# schematic.net
KiCad netlist of a schematic drawn in EAGLE
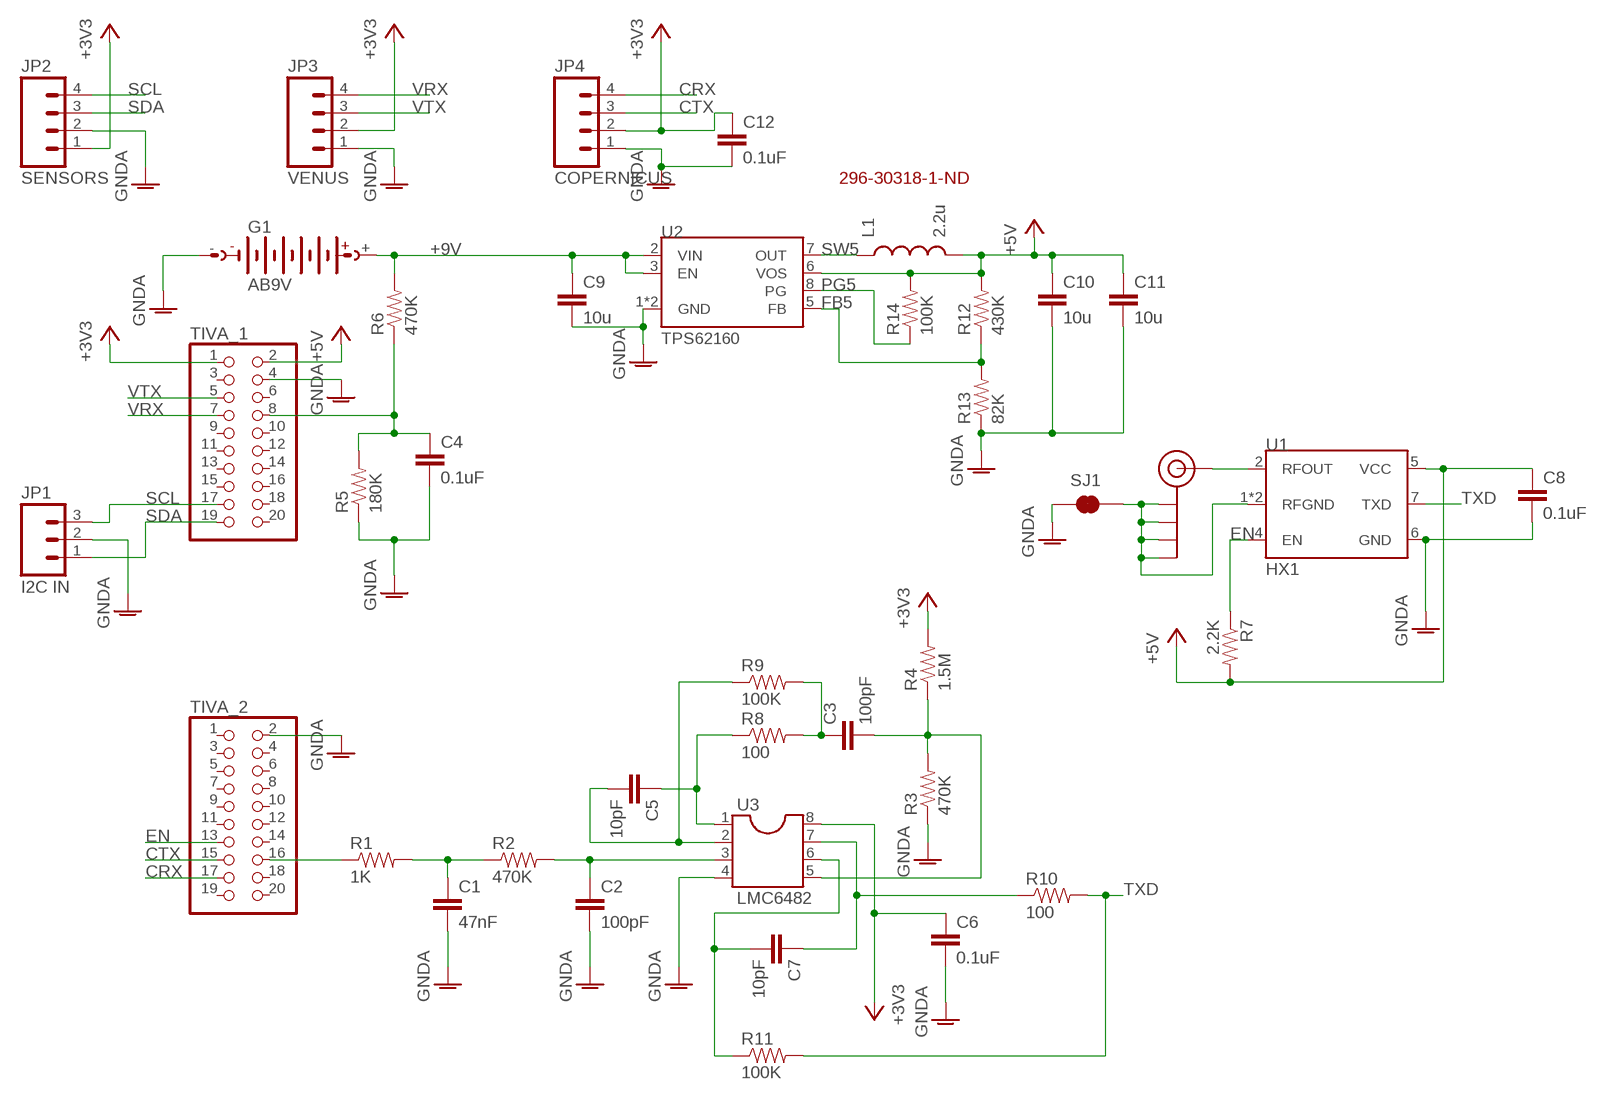
[diagram p0: schematic, sheet 1]

(export (version "E")
  (design (tool "Eeschema 10.0.6"))
  (components
    (comp (ref "C1")
      (value "47nF")
      (footprint "eagle-import:0805")
      (libsource (lib "eagle-import") (part "CAP0805"))
    )
    (comp (ref "C2")
      (value "100pF")
      (footprint "eagle-import:0805")
      (libsource (lib "eagle-import") (part "CAP0805"))
    )
    (comp (ref "C3")
      (value "100pF")
      (footprint "eagle-import:0805")
      (libsource (lib "eagle-import") (part "CAP0805"))
    )
    (comp (ref "C4")
      (value "0.1uF")
      (footprint "eagle-import:0805")
      (libsource (lib "eagle-import") (part "CAP0805"))
    )
    (comp (ref "C5")
      (value "10pF")
      (footprint "eagle-import:0805")
      (libsource (lib "eagle-import") (part "CAP0805"))
    )
    (comp (ref "C6")
      (value "0.1uF")
      (footprint "eagle-import:0805")
      (libsource (lib "eagle-import") (part "CAP0805"))
    )
    (comp (ref "C7")
      (value "10pF")
      (footprint "eagle-import:0805")
      (libsource (lib "eagle-import") (part "CAP0805"))
    )
    (comp (ref "C8")
      (value "0.1uF")
      (footprint "eagle-import:0805")
      (libsource (lib "eagle-import") (part "CAP0805"))
    )
    (comp (ref "C9")
      (value "10u")
      (footprint "eagle-import:0805")
      (libsource (lib "eagle-import") (part "CAP0805"))
    )
    (comp (ref "C10")
      (value "10u")
      (footprint "eagle-import:0805")
      (libsource (lib "eagle-import") (part "CAP0805"))
    )
    (comp (ref "C11")
      (value "10u")
      (footprint "eagle-import:0805")
      (libsource (lib "eagle-import") (part "CAP0805"))
    )
    (comp (ref "C12")
      (value "0.1uF")
      (footprint "eagle-import:0805")
      (libsource (lib "eagle-import") (part "CAP0805"))
    )
    (comp (ref "G1")
      (value "AB9V")
      (footprint "eagle-import:AB9V")
      (libsource (lib "eagle-import") (part "AB9V"))
    )
    (comp (ref "J1")
      (value "SMA_EDGE")
      (footprint "eagle-import:SMA-EDGE")
      (libsource (lib "eagle-import") (part "SMA_EDGE"))
    )
    (comp (ref "JP1")
      (value "I2C IN")
      (footprint "eagle-import:1X03")
      (libsource (lib "eagle-import") (part "M03PTH"))
    )
    (comp (ref "JP2")
      (value "SENSORS")
      (footprint "eagle-import:1X04")
      (libsource (lib "eagle-import") (part "M04PTH"))
    )
    (comp (ref "JP3")
      (value "VENUS")
      (footprint "eagle-import:1X04")
      (libsource (lib "eagle-import") (part "M04PTH"))
    )
    (comp (ref "JP4")
      (value "COPERNICUS")
      (footprint "eagle-import:1X04")
      (libsource (lib "eagle-import") (part "M04PTH"))
    )
    (comp (ref "L1")
      (value "2.2u")
      (footprint "eagle-import:1008")
      (libsource (lib "eagle-import") (part "INDUCTOR"))
    )
    (comp (ref "R1")
      (value "1K")
      (footprint "eagle-import:0805")
      (libsource (lib "eagle-import") (part "RESISTOR0805-RES"))
    )
    (comp (ref "R2")
      (value "470K")
      (footprint "eagle-import:0805")
      (libsource (lib "eagle-import") (part "RESISTOR0805-RES"))
    )
    (comp (ref "R3")
      (value "470K")
      (footprint "eagle-import:0805")
      (libsource (lib "eagle-import") (part "RESISTOR0805-RES"))
    )
    (comp (ref "R4")
      (value "1.5M")
      (footprint "eagle-import:0805")
      (libsource (lib "eagle-import") (part "RESISTOR0805-RES"))
    )
    (comp (ref "R5")
      (value "180K")
      (footprint "eagle-import:0805")
      (libsource (lib "eagle-import") (part "RESISTOR0805-RES"))
    )
    (comp (ref "R6")
      (value "470K")
      (footprint "eagle-import:0805")
      (libsource (lib "eagle-import") (part "RESISTOR0805-RES"))
    )
    (comp (ref "R7")
      (value "2.2K")
      (footprint "eagle-import:0805")
      (libsource (lib "eagle-import") (part "RESISTOR0805-RES"))
    )
    (comp (ref "R8")
      (value "100")
      (footprint "eagle-import:0805")
      (libsource (lib "eagle-import") (part "RESISTOR0805-RES"))
    )
    (comp (ref "R9")
      (value "100K")
      (footprint "eagle-import:0805")
      (libsource (lib "eagle-import") (part "RESISTOR0805-RES"))
    )
    (comp (ref "R10")
      (value "100")
      (footprint "eagle-import:0805")
      (libsource (lib "eagle-import") (part "RESISTOR0805-RES"))
    )
    (comp (ref "R11")
      (value "100K")
      (footprint "eagle-import:0805")
      (libsource (lib "eagle-import") (part "RESISTOR0805-RES"))
    )
    (comp (ref "R12")
      (value "430K")
      (footprint "eagle-import:0805")
      (libsource (lib "eagle-import") (part "RESISTOR0805-RES"))
    )
    (comp (ref "R13")
      (value "82K")
      (footprint "eagle-import:0805")
      (libsource (lib "eagle-import") (part "RESISTOR0805-RES"))
    )
    (comp (ref "R14")
      (value "100K")
      (footprint "eagle-import:0805")
      (libsource (lib "eagle-import") (part "RESISTOR0805-RES"))
    )
    (comp (ref "SJ1")
      (value "JUMPER-PAD-2-NC_BY_TRACE")
      (footprint "eagle-import:PAD-JUMPER-2-NC_BY_TRACE_YES_SILK")
      (libsource (lib "eagle-import") (part "JUMPER-PAD-2-NC_BY_TRACE"))
    )
    (comp (ref "TIVA_1")
      (value "PINHD-2X10")
      (footprint "eagle-import:2X10")
      (libsource (lib "eagle-import") (part "PINHD-2X10"))
    )
    (comp (ref "TIVA_2")
      (value "PINHD-2X10")
      (footprint "eagle-import:2X10")
      (libsource (lib "eagle-import") (part "PINHD-2X10"))
    )
    (comp (ref "U1")
      (value "HX1")
      (footprint "eagle-import:1X12")
      (libsource (lib "eagle-import") (part "HX1"))
    )
    (comp (ref "U2")
      (value "TPS62160")
      (footprint "eagle-import:MSOP8")
      (libsource (lib "eagle-import") (part "TPS62160"))
    )
    (comp (ref "U3")
      (value "LMC6482")
      (footprint "eagle-import:DIL08")
      (libsource (lib "eagle-import") (part "DIL8"))
    )
  )
  (nets
    (net (code "1") (name "+3V3") (class "Default")
      (node (ref "C12") (pin "1") (pinfunction "1_1") (pintype "passive"))
      (node (ref "C6") (pin "1") (pinfunction "1_1") (pintype "passive"))
      (node (ref "JP2") (pin "1") (pinfunction "1_1") (pintype "passive"))
      (node (ref "JP3") (pin "2") (pinfunction "2_2") (pintype "passive"))
      (node (ref "JP4") (pin "2") (pinfunction "2_2") (pintype "passive"))
      (node (ref "R4") (pin "2") (pinfunction "2_2") (pintype "passive"))
      (node (ref "TIVA_1") (pin "1") (pinfunction "1_1") (pintype "passive"))
      (node (ref "U3") (pin "8") (pinfunction "8_8") (pintype "passive"))
    )
    (net (code "2") (name "+5V") (class "Default")
      (node (ref "C10") (pin "1") (pinfunction "1_1") (pintype "passive"))
      (node (ref "C11") (pin "1") (pinfunction "1_1") (pintype "passive"))
      (node (ref "C8") (pin "1") (pinfunction "1_1") (pintype "passive"))
      (node (ref "L1") (pin "2") (pinfunction "2_2") (pintype "passive"))
      (node (ref "R12") (pin "2") (pinfunction "2_2") (pintype "passive"))
      (node (ref "R14") (pin "2") (pinfunction "2_2") (pintype "passive"))
      (node (ref "R7") (pin "2") (pinfunction "2_2") (pintype "passive"))
      (node (ref "TIVA_1") (pin "2") (pinfunction "2_2") (pintype "passive"))
      (node (ref "U1") (pin "5") (pinfunction "VCC_5") (pintype "power_in"))
      (node (ref "U2") (pin "6") (pinfunction "VOS_6") (pintype "input"))
    )
    (net (code "3") (name "/+9V") (class "Default")
      (node (ref "C9") (pin "1") (pinfunction "1_1") (pintype "passive"))
      (node (ref "G1") (pin "+") (pinfunction "+_+") (pintype "passive"))
      (node (ref "R6") (pin "2") (pinfunction "2_2") (pintype "passive"))
      (node (ref "U2") (pin "2") (pinfunction "VIN_2") (pintype "power_in"))
      (node (ref "U2") (pin "3") (pinfunction "EN_3") (pintype "input"))
    )
    (net (code "4") (name "/CRX") (class "Default")
      (node (ref "JP4") (pin "4") (pinfunction "4_4") (pintype "passive"))
      (node (ref "TIVA_2") (pin "17") (pinfunction "17_17") (pintype "passive"))
    )
    (net (code "5") (name "/CTX") (class "Default")
      (node (ref "JP4") (pin "3") (pinfunction "3_3") (pintype "passive"))
      (node (ref "TIVA_2") (pin "15") (pinfunction "15_15") (pintype "passive"))
    )
    (net (code "6") (name "/EN") (class "Default")
      (node (ref "R7") (pin "1") (pinfunction "1_1") (pintype "passive"))
      (node (ref "TIVA_2") (pin "13") (pinfunction "13_13") (pintype "passive"))
      (node (ref "U1") (pin "4") (pinfunction "EN_4") (pintype "input"))
    )
    (net (code "7") (name "/FB5") (class "Default")
      (node (ref "R12") (pin "1") (pinfunction "1_1") (pintype "passive"))
      (node (ref "R13") (pin "2") (pinfunction "2_2") (pintype "passive"))
      (node (ref "U2") (pin "5") (pinfunction "FB_5") (pintype "input"))
    )
    (net (code "8") (name "/PG5") (class "Default")
      (node (ref "R14") (pin "1") (pinfunction "1_1") (pintype "passive"))
      (node (ref "U2") (pin "8") (pinfunction "PG_8") (pintype "open_collector"))
    )
    (net (code "9") (name "/SCL") (class "Default")
      (node (ref "JP1") (pin "3") (pinfunction "3_3") (pintype "passive"))
      (node (ref "JP2") (pin "4") (pinfunction "4_4") (pintype "passive"))
      (node (ref "TIVA_1") (pin "17") (pinfunction "17_17") (pintype "passive"))
    )
    (net (code "10") (name "/SDA") (class "Default")
      (node (ref "JP1") (pin "1") (pinfunction "1_1") (pintype "passive"))
      (node (ref "JP2") (pin "3") (pinfunction "3_3") (pintype "passive"))
      (node (ref "TIVA_1") (pin "19") (pinfunction "19_19") (pintype "passive"))
    )
    (net (code "11") (name "/SW5") (class "Default")
      (node (ref "L1") (pin "1") (pinfunction "1_1") (pintype "passive"))
      (node (ref "U2") (pin "7") (pinfunction "OUT_7") (pintype "output"))
    )
    (net (code "12") (name "/TXD") (class "Default")
      (node (ref "R10") (pin "2") (pinfunction "2_2") (pintype "passive"))
      (node (ref "R11") (pin "2") (pinfunction "2_2") (pintype "passive"))
      (node (ref "U1") (pin "7") (pinfunction "TXD_7") (pintype "input"))
    )
    (net (code "13") (name "/VRX") (class "Default")
      (node (ref "JP3") (pin "4") (pinfunction "4_4") (pintype "passive"))
      (node (ref "TIVA_1") (pin "7") (pinfunction "7_7") (pintype "passive"))
    )
    (net (code "14") (name "/VTX") (class "Default")
      (node (ref "JP3") (pin "3") (pinfunction "3_3") (pintype "passive"))
      (node (ref "TIVA_1") (pin "5") (pinfunction "5_5") (pintype "passive"))
    )
    (net (code "15") (name "GNDA") (class "Default")
      (node (ref "C1") (pin "2") (pinfunction "2_2") (pintype "passive"))
      (node (ref "C10") (pin "2") (pinfunction "2_2") (pintype "passive"))
      (node (ref "C11") (pin "2") (pinfunction "2_2") (pintype "passive"))
      (node (ref "C12") (pin "2") (pinfunction "2_2") (pintype "passive"))
      (node (ref "C2") (pin "2") (pinfunction "2_2") (pintype "passive"))
      (node (ref "C4") (pin "2") (pinfunction "2_2") (pintype "passive"))
      (node (ref "C6") (pin "2") (pinfunction "2_2") (pintype "passive"))
      (node (ref "C8") (pin "2") (pinfunction "2_2") (pintype "passive"))
      (node (ref "C9") (pin "2") (pinfunction "2_2") (pintype "passive"))
      (node (ref "G1") (pin "-") (pinfunction "-_-") (pintype "passive"))
      (node (ref "JP1") (pin "2") (pinfunction "2_2") (pintype "passive"))
      (node (ref "JP2") (pin "2") (pinfunction "2_2") (pintype "passive"))
      (node (ref "JP3") (pin "1") (pinfunction "1_1") (pintype "passive"))
      (node (ref "JP4") (pin "1") (pinfunction "1_1") (pintype "passive"))
      (node (ref "R13") (pin "1") (pinfunction "1_1") (pintype "passive"))
      (node (ref "R3") (pin "1") (pinfunction "1_1") (pintype "passive"))
      (node (ref "R5") (pin "1") (pinfunction "1_1") (pintype "passive"))
      (node (ref "SJ1") (pin "1") (pinfunction "1_1") (pintype "passive"))
      (node (ref "TIVA_1") (pin "4") (pinfunction "4_4") (pintype "passive"))
      (node (ref "TIVA_2") (pin "2") (pinfunction "2_2") (pintype "passive"))
      (node (ref "U1") (pin "6") (pinfunction "GND_6") (pintype "power_in"))
      (node (ref "U2") (pin "1") (pinfunction "GND_1") (pintype "power_in"))
      (node (ref "U2") (pin "4") (pinfunction "GND_4") (pintype "power_in"))
      (node (ref "U3") (pin "4") (pinfunction "4_4") (pintype "passive"))
    )
    (net (code "16") (name "Net-(C1-Pad1)") (class "Default")
      (node (ref "C1") (pin "1") (pinfunction "1_1") (pintype "passive"))
      (node (ref "R1") (pin "2") (pinfunction "2_2") (pintype "passive"))
      (node (ref "R2") (pin "1") (pinfunction "1_1") (pintype "passive"))
    )
    (net (code "17") (name "Net-(C2-Pad1)") (class "Default")
      (node (ref "C2") (pin "1") (pinfunction "1_1") (pintype "passive"))
      (node (ref "R2") (pin "2") (pinfunction "2_2") (pintype "passive"))
      (node (ref "U3") (pin "3") (pinfunction "3_3") (pintype "passive"))
    )
    (net (code "18") (name "Net-(C3-Pad1)") (class "Default")
      (node (ref "C3") (pin "1") (pinfunction "1_1") (pintype "passive"))
      (node (ref "R8") (pin "2") (pinfunction "2_2") (pintype "passive"))
      (node (ref "R9") (pin "2") (pinfunction "2_2") (pintype "passive"))
    )
    (net (code "19") (name "Net-(C3-Pad2)") (class "Default")
      (node (ref "C3") (pin "2") (pinfunction "2_2") (pintype "passive"))
      (node (ref "R3") (pin "2") (pinfunction "2_2") (pintype "passive"))
      (node (ref "R4") (pin "1") (pinfunction "1_1") (pintype "passive"))
      (node (ref "U3") (pin "5") (pinfunction "5_5") (pintype "passive"))
    )
    (net (code "20") (name "Net-(C4-Pad1)") (class "Default")
      (node (ref "C4") (pin "1") (pinfunction "1_1") (pintype "passive"))
      (node (ref "R5") (pin "2") (pinfunction "2_2") (pintype "passive"))
      (node (ref "R6") (pin "1") (pinfunction "1_1") (pintype "passive"))
      (node (ref "TIVA_1") (pin "8") (pinfunction "8_8") (pintype "passive"))
    )
    (net (code "21") (name "Net-(C5-Pad1)") (class "Default")
      (node (ref "C5") (pin "1") (pinfunction "1_1") (pintype "passive"))
      (node (ref "R8") (pin "1") (pinfunction "1_1") (pintype "passive"))
      (node (ref "U3") (pin "1") (pinfunction "1_1") (pintype "passive"))
    )
    (net (code "22") (name "Net-(C5-Pad2)") (class "Default")
      (node (ref "C5") (pin "2") (pinfunction "2_2") (pintype "passive"))
      (node (ref "R9") (pin "1") (pinfunction "1_1") (pintype "passive"))
      (node (ref "U3") (pin "2") (pinfunction "2_2") (pintype "passive"))
    )
    (net (code "23") (name "Net-(C7-Pad1)") (class "Default")
      (node (ref "C7") (pin "1") (pinfunction "1_1") (pintype "passive"))
      (node (ref "R10") (pin "1") (pinfunction "1_1") (pintype "passive"))
      (node (ref "U3") (pin "7") (pinfunction "7_7") (pintype "passive"))
    )
    (net (code "24") (name "Net-(C7-Pad2)") (class "Default")
      (node (ref "C7") (pin "2") (pinfunction "2_2") (pintype "passive"))
      (node (ref "R11") (pin "1") (pinfunction "1_1") (pintype "passive"))
      (node (ref "U3") (pin "6") (pinfunction "6_6") (pintype "passive"))
    )
    (net (code "25") (name "Net-(J1-GND-PadGND@0)") (class "Default")
      (node (ref "J1") (pin "GND@0") (pinfunction "GND_GND@0") (pintype "bidirectional"))
      (node (ref "J1") (pin "GND@1") (pinfunction "GND_GND@1") (pintype "bidirectional"))
      (node (ref "J1") (pin "GND@2") (pinfunction "GND_GND@2") (pintype "bidirectional"))
      (node (ref "J1") (pin "GND@3") (pinfunction "GND_GND@3") (pintype "bidirectional"))
      (node (ref "SJ1") (pin "2") (pinfunction "2_2") (pintype "passive"))
      (node (ref "U1") (pin "1") (pinfunction "RFGND_1") (pintype "power_in"))
      (node (ref "U1") (pin "3") (pinfunction "RFGND_3") (pintype "power_in"))
    )
    (net (code "26") (name "Net-(J1-SIGNAL)") (class "Default")
      (node (ref "J1") (pin "SIG") (pinfunction "SIGNAL_SIG") (pintype "bidirectional"))
      (node (ref "U1") (pin "2") (pinfunction "RFOUT_2") (pintype "output"))
    )
    (net (code "27") (name "Net-(R1-Pad1)") (class "Default")
      (node (ref "R1") (pin "1") (pinfunction "1_1") (pintype "passive"))
      (node (ref "TIVA_2") (pin "16") (pinfunction "16_16") (pintype "passive"))
    )
    (net (code "28") (name "unconnected-(TIVA_1-Pad3)") (class "Default")
      (node (ref "TIVA_1") (pin "3") (pinfunction "3_3") (pintype "passive"))
    )
    (net (code "29") (name "unconnected-(TIVA_1-Pad6)") (class "Default")
      (node (ref "TIVA_1") (pin "6") (pinfunction "6_6") (pintype "passive"))
    )
    (net (code "30") (name "unconnected-(TIVA_1-Pad9)") (class "Default")
      (node (ref "TIVA_1") (pin "9") (pinfunction "9_9") (pintype "passive"))
    )
    (net (code "31") (name "unconnected-(TIVA_1-Pad10)") (class "Default")
      (node (ref "TIVA_1") (pin "10") (pinfunction "10_10") (pintype "passive"))
    )
    (net (code "32") (name "unconnected-(TIVA_1-Pad11)") (class "Default")
      (node (ref "TIVA_1") (pin "11") (pinfunction "11_11") (pintype "passive"))
    )
    (net (code "33") (name "unconnected-(TIVA_1-Pad12)") (class "Default")
      (node (ref "TIVA_1") (pin "12") (pinfunction "12_12") (pintype "passive"))
    )
    (net (code "34") (name "unconnected-(TIVA_1-Pad13)") (class "Default")
      (node (ref "TIVA_1") (pin "13") (pinfunction "13_13") (pintype "passive"))
    )
    (net (code "35") (name "unconnected-(TIVA_1-Pad14)") (class "Default")
      (node (ref "TIVA_1") (pin "14") (pinfunction "14_14") (pintype "passive"))
    )
    (net (code "36") (name "unconnected-(TIVA_1-Pad15)") (class "Default")
      (node (ref "TIVA_1") (pin "15") (pinfunction "15_15") (pintype "passive"))
    )
    (net (code "37") (name "unconnected-(TIVA_1-Pad16)") (class "Default")
      (node (ref "TIVA_1") (pin "16") (pinfunction "16_16") (pintype "passive"))
    )
    (net (code "38") (name "unconnected-(TIVA_1-Pad18)") (class "Default")
      (node (ref "TIVA_1") (pin "18") (pinfunction "18_18") (pintype "passive"))
    )
    (net (code "39") (name "unconnected-(TIVA_1-Pad20)") (class "Default")
      (node (ref "TIVA_1") (pin "20") (pinfunction "20_20") (pintype "passive"))
    )
    (net (code "40") (name "unconnected-(TIVA_2-Pad1)") (class "Default")
      (node (ref "TIVA_2") (pin "1") (pinfunction "1_1") (pintype "passive"))
    )
    (net (code "41") (name "unconnected-(TIVA_2-Pad3)") (class "Default")
      (node (ref "TIVA_2") (pin "3") (pinfunction "3_3") (pintype "passive"))
    )
    (net (code "42") (name "unconnected-(TIVA_2-Pad4)") (class "Default")
      (node (ref "TIVA_2") (pin "4") (pinfunction "4_4") (pintype "passive"))
    )
    (net (code "43") (name "unconnected-(TIVA_2-Pad5)") (class "Default")
      (node (ref "TIVA_2") (pin "5") (pinfunction "5_5") (pintype "passive"))
    )
    (net (code "44") (name "unconnected-(TIVA_2-Pad6)") (class "Default")
      (node (ref "TIVA_2") (pin "6") (pinfunction "6_6") (pintype "passive"))
    )
    (net (code "45") (name "unconnected-(TIVA_2-Pad7)") (class "Default")
      (node (ref "TIVA_2") (pin "7") (pinfunction "7_7") (pintype "passive"))
    )
    (net (code "46") (name "unconnected-(TIVA_2-Pad8)") (class "Default")
      (node (ref "TIVA_2") (pin "8") (pinfunction "8_8") (pintype "passive"))
    )
    (net (code "47") (name "unconnected-(TIVA_2-Pad9)") (class "Default")
      (node (ref "TIVA_2") (pin "9") (pinfunction "9_9") (pintype "passive"))
    )
    (net (code "48") (name "unconnected-(TIVA_2-Pad10)") (class "Default")
      (node (ref "TIVA_2") (pin "10") (pinfunction "10_10") (pintype "passive"))
    )
    (net (code "49") (name "unconnected-(TIVA_2-Pad11)") (class "Default")
      (node (ref "TIVA_2") (pin "11") (pinfunction "11_11") (pintype "passive"))
    )
    (net (code "50") (name "unconnected-(TIVA_2-Pad12)") (class "Default")
      (node (ref "TIVA_2") (pin "12") (pinfunction "12_12") (pintype "passive"))
    )
    (net (code "51") (name "unconnected-(TIVA_2-Pad14)") (class "Default")
      (node (ref "TIVA_2") (pin "14") (pinfunction "14_14") (pintype "passive"))
    )
    (net (code "52") (name "unconnected-(TIVA_2-Pad18)") (class "Default")
      (node (ref "TIVA_2") (pin "18") (pinfunction "18_18") (pintype "passive"))
    )
    (net (code "53") (name "unconnected-(TIVA_2-Pad19)") (class "Default")
      (node (ref "TIVA_2") (pin "19") (pinfunction "19_19") (pintype "passive"))
    )
    (net (code "54") (name "unconnected-(TIVA_2-Pad20)") (class "Default")
      (node (ref "TIVA_2") (pin "20") (pinfunction "20_20") (pintype "passive"))
    )
  )
)
